# BreakoutPins.net
KiCad netlist of a schematic drawn in Altium Designer
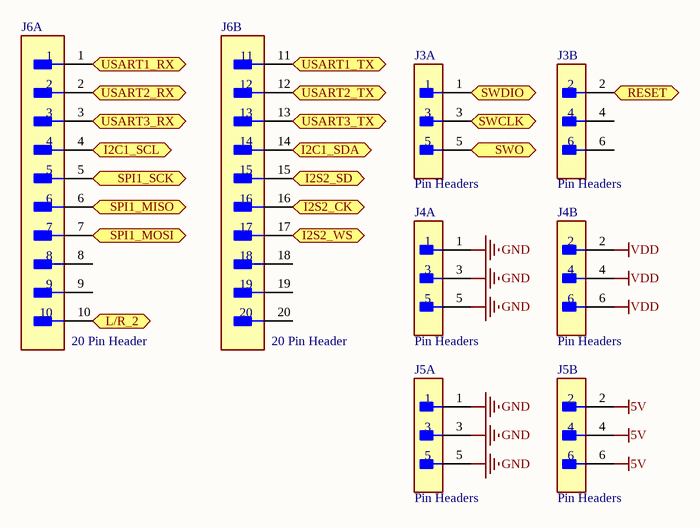
[diagram p0: BreakoutPins.SchDoc]

(export (version "E")
  (design (tool "Eeschema 10.0.6"))
  (components
    (comp (ref "J3")
      (value "Pin Headers")
      (footprint "FP-M20-9980346-MFG")
      (description "CONN HEADER VERT 6POS 2.54MM\r\nM20-9980346")
      (fields (field (name "MANUFACTURER PART NUMBER") "M20-9980346") (field (name "MANUFACTURER") "Harwin"))
      (libsource (lib "Altium Content Vault") (part "2654a11fb13586ecb194516b1c997bc"))
    )
    (comp (ref "J4")
      (value "Pin Headers")
      (footprint "FP-M20-9980346-MFG")
      (description "CONN HEADER VERT 6POS 2.54MM\r\nM20-9980346")
      (fields (field (name "MANUFACTURER PART NUMBER") "M20-9980346") (field (name "MANUFACTURER") "Harwin"))
      (libsource (lib "Altium Content Vault") (part "2654a11fb13586ecb194516b1c997bc"))
    )
    (comp (ref "J5")
      (value "Pin Headers")
      (footprint "FP-M20-9980346-MFG")
      (description "CONN HEADER VERT 6POS 2.54MM\r\nM20-9980346")
      (fields (field (name "MANUFACTURER PART NUMBER") "M20-9980346") (field (name "MANUFACTURER") "Harwin"))
      (libsource (lib "Altium Content Vault") (part "2654a11fb13586ecb194516b1c997bc"))
    )
    (comp (ref "J6")
      (value "20 Pin Header")
      (footprint "FP-TSW-110-08-G-D-MFG")
      (description "CONN HEADER VERT 20POS 2.54MM\r\nTSW-110-08-G-D")
      (fields
        (field (name "MANUFACTURER") "Samtec")
        (field (name "MANUFACTURER PART NUMBER") "TSW-110-08-G-D")
      )
      (libsource (lib "Altium Content Vault") (part "77e5b6e48cf913a9c6d5f7856d88bd2"))
    )
  )
  (nets
    (net (code "1") (name "/I2C1_SCL") (class "Default")
      (node (ref "J6") (pin "4") (pinfunction "4_4") (pintype "passive"))
    )
    (net (code "2") (name "/I2C1_SDA") (class "Default")
      (node (ref "J6") (pin "14") (pinfunction "14_14") (pintype "passive"))
    )
    (net (code "3") (name "/I2S2_CK") (class "Default")
      (node (ref "J6") (pin "16") (pinfunction "16_16") (pintype "passive"))
    )
    (net (code "4") (name "/I2S2_SD") (class "Default")
      (node (ref "J6") (pin "15") (pinfunction "15_15") (pintype "passive"))
    )
    (net (code "5") (name "/I2S2_WS") (class "Default")
      (node (ref "J6") (pin "17") (pinfunction "17_17") (pintype "passive"))
    )
    (net (code "6") (name "/L{slash}R_2") (class "Default")
      (node (ref "J6") (pin "10") (pinfunction "10_10") (pintype "passive"))
    )
    (net (code "7") (name "/RESET") (class "Default")
      (node (ref "J3") (pin "2") (pinfunction "2_2") (pintype "passive"))
    )
    (net (code "8") (name "/SPI1_MISO") (class "Default")
      (node (ref "J6") (pin "6") (pinfunction "6_6") (pintype "passive"))
    )
    (net (code "9") (name "/SPI1_MOSI") (class "Default")
      (node (ref "J6") (pin "7") (pinfunction "7_7") (pintype "passive"))
    )
    (net (code "10") (name "/SPI1_SCK") (class "Default")
      (node (ref "J6") (pin "5") (pinfunction "5_5") (pintype "passive"))
    )
    (net (code "11") (name "/SWCLK") (class "Default")
      (node (ref "J3") (pin "3") (pinfunction "3_3") (pintype "passive"))
    )
    (net (code "12") (name "/SWDIO") (class "Default")
      (node (ref "J3") (pin "1") (pinfunction "1_1") (pintype "passive"))
    )
    (net (code "13") (name "/SWO") (class "Default")
      (node (ref "J3") (pin "5") (pinfunction "5_5") (pintype "passive"))
    )
    (net (code "14") (name "/USART1_RX") (class "Default")
      (node (ref "J6") (pin "1") (pinfunction "1_1") (pintype "passive"))
    )
    (net (code "15") (name "/USART1_TX") (class "Default")
      (node (ref "J6") (pin "11") (pinfunction "11_11") (pintype "passive"))
    )
    (net (code "16") (name "/USART2_RX") (class "Default")
      (node (ref "J6") (pin "2") (pinfunction "2_2") (pintype "passive"))
    )
    (net (code "17") (name "/USART2_TX") (class "Default")
      (node (ref "J6") (pin "12") (pinfunction "12_12") (pintype "passive"))
    )
    (net (code "18") (name "/USART3_RX") (class "Default")
      (node (ref "J6") (pin "3") (pinfunction "3_3") (pintype "passive"))
    )
    (net (code "19") (name "/USART3_TX") (class "Default")
      (node (ref "J6") (pin "13") (pinfunction "13_13") (pintype "passive"))
    )
    (net (code "20") (name "5V") (class "Default")
      (node (ref "J5") (pin "2") (pinfunction "2_2") (pintype "passive"))
      (node (ref "J5") (pin "4") (pinfunction "4_4") (pintype "passive"))
      (node (ref "J5") (pin "6") (pinfunction "6_6") (pintype "passive"))
    )
    (net (code "21") (name "GND") (class "Default")
      (node (ref "J4") (pin "1") (pinfunction "1_1") (pintype "passive"))
      (node (ref "J4") (pin "3") (pinfunction "3_3") (pintype "passive"))
      (node (ref "J4") (pin "5") (pinfunction "5_5") (pintype "passive"))
      (node (ref "J5") (pin "1") (pinfunction "1_1") (pintype "passive"))
      (node (ref "J5") (pin "3") (pinfunction "3_3") (pintype "passive"))
      (node (ref "J5") (pin "5") (pinfunction "5_5") (pintype "passive"))
    )
    (net (code "22") (name "VDD") (class "Default")
      (node (ref "J4") (pin "2") (pinfunction "2_2") (pintype "passive"))
      (node (ref "J4") (pin "4") (pinfunction "4_4") (pintype "passive"))
      (node (ref "J4") (pin "6") (pinfunction "6_6") (pintype "passive"))
    )
    (net (code "23") (name "unconnected-(J3-Pad4)") (class "Default")
      (node (ref "J3") (pin "4") (pinfunction "4_4") (pintype "passive"))
    )
    (net (code "24") (name "unconnected-(J3-Pad6)") (class "Default")
      (node (ref "J3") (pin "6") (pinfunction "6_6") (pintype "passive"))
    )
    (net (code "25") (name "unconnected-(J6-Pad8)") (class "Default")
      (node (ref "J6") (pin "8") (pinfunction "8_8") (pintype "passive"))
    )
    (net (code "26") (name "unconnected-(J6-Pad9)") (class "Default")
      (node (ref "J6") (pin "9") (pinfunction "9_9") (pintype "passive"))
    )
    (net (code "27") (name "unconnected-(J6-Pad18)") (class "Default")
      (node (ref "J6") (pin "18") (pinfunction "18_18") (pintype "passive"))
    )
    (net (code "28") (name "unconnected-(J6-Pad19)") (class "Default")
      (node (ref "J6") (pin "19") (pinfunction "19_19") (pintype "passive"))
    )
    (net (code "29") (name "unconnected-(J6-Pad20)") (class "Default")
      (node (ref "J6") (pin "20") (pinfunction "20_20") (pintype "passive"))
    )
  )
)
